# edi_1.net
KiCad netlist of a schematic drawn in EAGLE
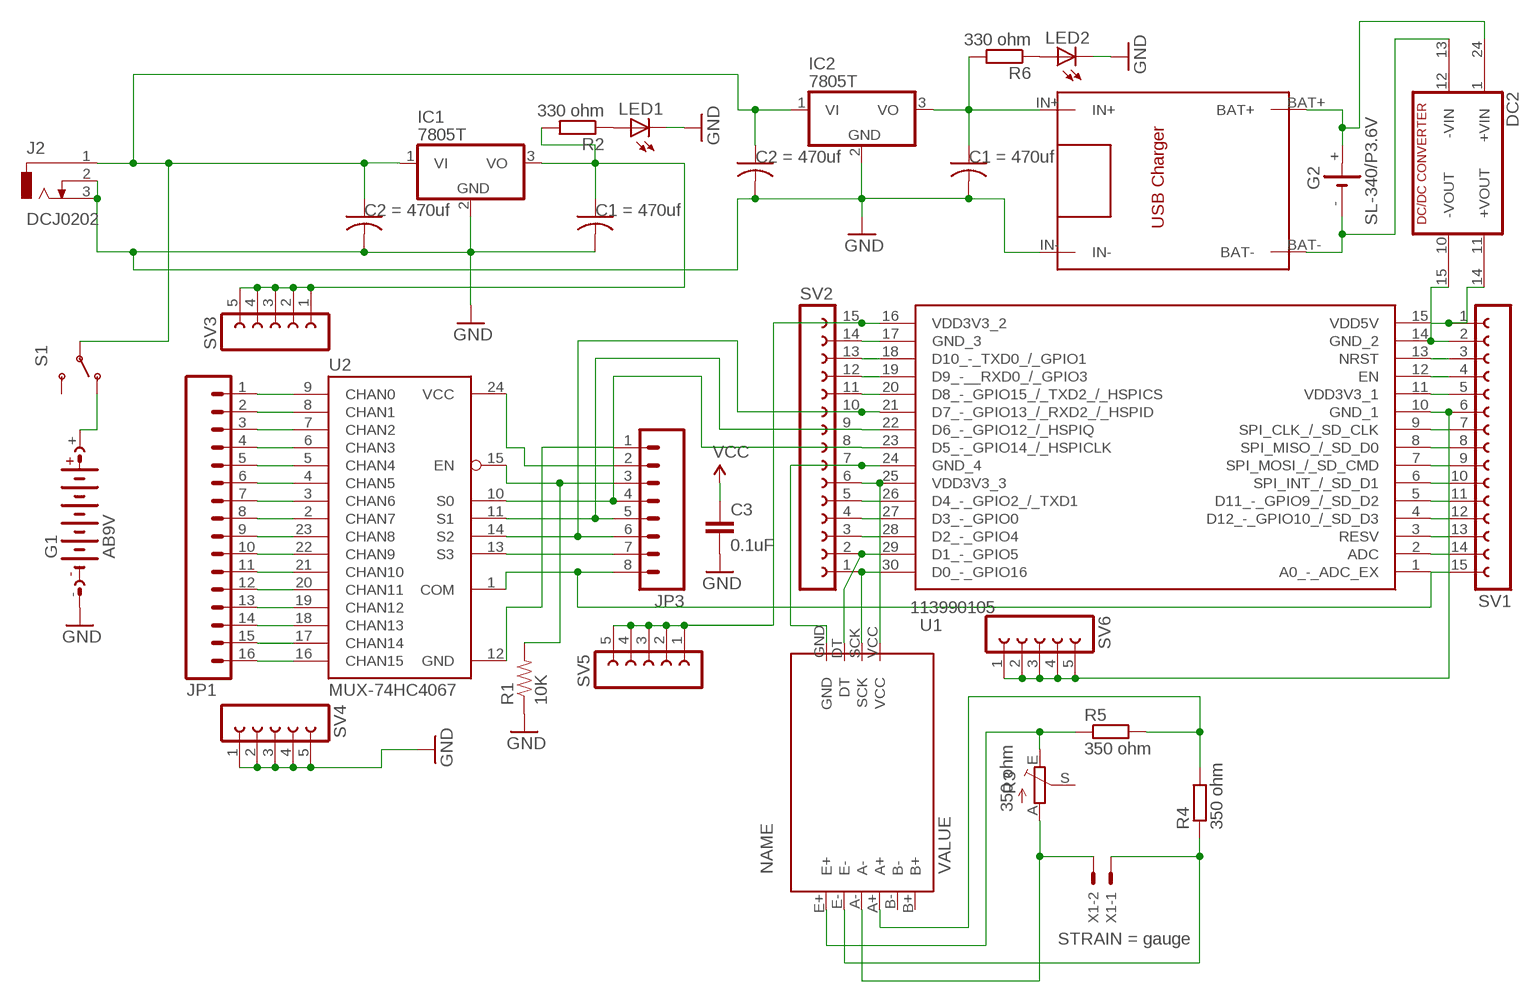
[diagram p0: schematic, sheet 1]

(export (version "E")
  (design (tool "Eeschema 10.0.6"))
  (components
    (comp (ref "C1")
      (value "C-US025-024X044")
      (footprint "eagle-import:C025-024X044")
      (fields (field (name "C2") "470uf"))
      (libsource (lib "eagle-import") (part "C-US025-024X044"))
    )
    (comp (ref "C2")
      (value "C-US025-024X044")
      (footprint "eagle-import:C025-024X044")
      (fields (field (name "C1") "470uf") (field (name "POPULARITY") "470uf"))
      (libsource (lib "eagle-import") (part "C-US025-024X044"))
    )
    (comp (ref "C3")
      (value "0.1uF")
      (footprint "eagle-import:0603")
      (libsource (lib "eagle-import") (part "CAP0603"))
    )
    (comp (ref "C4")
      (value "C-US025-024X044")
      (footprint "eagle-import:C025-024X044")
      (fields (field (name "C2") "470uf"))
      (libsource (lib "eagle-import") (part "C-US025-024X044"))
    )
    (comp (ref "C5")
      (value "C-US025-024X044")
      (footprint "eagle-import:C025-024X044")
      (fields (field (name "C1") "470uf") (field (name "POPULARITY") "470uf"))
      (libsource (lib "eagle-import") (part "C-US025-024X044"))
    )
    (comp (ref "DC2")
      (value "DC213R")
      (footprint "eagle-import:CMK")
      (libsource (lib "eagle-import") (part "DC213R"))
    )
    (comp (ref "G1")
      (value "AB9V")
      (footprint "eagle-import:AB9V")
      (libsource (lib "eagle-import") (part "AB9V"))
    )
    (comp (ref "G2")
      (value "SL-340/P3.6V")
      (footprint "eagle-import:SL-340_P3.6V")
      (libsource (lib "eagle-import") (part "SL-340/P3.6V"))
    )
    (comp (ref "IC1")
      (value "7805T")
      (footprint "eagle-import:TO220H")
      (libsource (lib "eagle-import") (part "78T05"))
    )
    (comp (ref "IC2")
      (value "7805T")
      (footprint "eagle-import:TO220H")
      (libsource (lib "eagle-import") (part "78T05"))
    )
    (comp (ref "J2")
      (value "DCJ0202")
      (footprint "eagle-import:DCJ0202")
      (libsource (lib "eagle-import") (part "DCJ0202"))
    )
    (comp (ref "JP1")
      (value "M16PTH")
      (footprint "eagle-import:1X16")
      (libsource (lib "eagle-import") (part "M16PTH"))
    )
    (comp (ref "JP3")
      (value "M081X08")
      (footprint "eagle-import:1X08")
      (libsource (lib "eagle-import") (part "M081X08"))
    )
    (comp (ref "LED1")
      (value "LEDLD260")
      (footprint "eagle-import:LD260")
      (libsource (lib "eagle-import") (part "LEDLD260"))
    )
    (comp (ref "LED2")
      (value "LEDLD260")
      (footprint "eagle-import:LD260")
      (libsource (lib "eagle-import") (part "LEDLD260"))
    )
    (comp (ref "R1")
      (value "10K")
      (footprint "eagle-import:0603")
      (libsource (lib "eagle-import") (part "RESISTOR0603"))
    )
    (comp (ref "R2")
      (value "330 ohm")
      (footprint "eagle-import:0204_5")
      (libsource (lib "eagle-import") (part "R-EU_0204/5"))
    )
    (comp (ref "R3")
      (value "350 ohm")
      (footprint "eagle-import:RJ9W")
      (libsource (lib "eagle-import") (part "TRIM_EU-RJ9W"))
    )
    (comp (ref "R4")
      (value "350 ohm")
      (footprint "eagle-import:0204_5")
      (libsource (lib "eagle-import") (part "R-EU_0204/5"))
    )
    (comp (ref "R5")
      (value "350 ohm")
      (footprint "eagle-import:0204_5")
      (libsource (lib "eagle-import") (part "R-EU_0204/5"))
    )
    (comp (ref "R6")
      (value "330 ohm")
      (footprint "eagle-import:0204_5")
      (libsource (lib "eagle-import") (part "R-EU_0204/5"))
    )
    (comp (ref "S1")
      (value "SWITCH-SPDTSMD")
      (footprint "eagle-import:SWITCH_SPDT_SMD")
      (libsource (lib "eagle-import") (part "SWITCH-SPDTSMD"))
    )
    (comp (ref "SV1")
      (value "FE15-1")
      (footprint "eagle-import:FE15")
      (libsource (lib "eagle-import") (part "FE15-1"))
    )
    (comp (ref "SV2")
      (value "FE15-1")
      (footprint "eagle-import:FE15")
      (libsource (lib "eagle-import") (part "FE15-1"))
    )
    (comp (ref "SV3")
      (value "FE05-1")
      (footprint "eagle-import:FE05-1")
      (libsource (lib "eagle-import") (part "FE05-1"))
    )
    (comp (ref "SV4")
      (value "FE05-1")
      (footprint "eagle-import:FE05-1")
      (libsource (lib "eagle-import") (part "FE05-1"))
    )
    (comp (ref "SV5")
      (value "FE05-1")
      (footprint "eagle-import:FE05-1")
      (libsource (lib "eagle-import") (part "FE05-1"))
    )
    (comp (ref "SV6")
      (value "FE05-1")
      (footprint "eagle-import:FE05-1")
      (libsource (lib "eagle-import") (part "FE05-1"))
    )
    (comp (ref "U$1")
      (value "TP4056")
      (footprint "eagle-import:TP4056")
      (libsource (lib "eagle-import") (part "TP4056"))
    )
    (comp (ref "U$2")
      (value "HX711A")
      (footprint "eagle-import:HX711")
      (libsource (lib "eagle-import") (part "HX711A"))
    )
    (comp (ref "U1")
      (value "113990105")
      (footprint "eagle-import:113990105")
      (fields (field (name "MOUSER_PART_NUMBER") "713-113990105"))
      (libsource (lib "eagle-import") (part "113990105"))
    )
    (comp (ref "U2")
      (value "MUX-74HC4067")
      (footprint "eagle-import:SSOP24")
      (libsource (lib "eagle-import") (part "MUX-74HC4067SMD"))
    )
    (comp (ref "X1")
      (value "22-23-2021")
      (footprint "eagle-import:22-23-2021")
      (fields (field (name "STRAIN") "gauge"))
      (libsource (lib "eagle-import") (part "22-23-2021"))
    )
  )
  (nets
    (net (code "1") (name "GND") (class "Default")
      (node (ref "C1") (pin "2") (pinfunction "2_2") (pintype "passive"))
      (node (ref "C2") (pin "2") (pinfunction "2_2") (pintype "passive"))
      (node (ref "C3") (pin "2") (pinfunction "2_2") (pintype "passive"))
      (node (ref "C4") (pin "2") (pinfunction "2_2") (pintype "passive"))
      (node (ref "C5") (pin "2") (pinfunction "2_2") (pintype "passive"))
      (node (ref "G1") (pin "-") (pinfunction "-_-") (pintype "passive"))
      (node (ref "IC1") (pin "2") (pinfunction "GND_2") (pintype "passive"))
      (node (ref "IC2") (pin "2") (pinfunction "GND_2") (pintype "passive"))
      (node (ref "J2") (pin "2") (pinfunction "2_2") (pintype "passive"))
      (node (ref "J2") (pin "3") (pinfunction "3_3") (pintype "passive"))
      (node (ref "LED1") (pin "K") (pinfunction "C_K") (pintype "passive"))
      (node (ref "LED2") (pin "K") (pinfunction "C_K") (pintype "passive"))
      (node (ref "R1") (pin "1") (pinfunction "1_1") (pintype "passive"))
      (node (ref "SV4") (pin "1") (pinfunction "1_1") (pintype "passive"))
      (node (ref "SV4") (pin "2") (pinfunction "2_2") (pintype "passive"))
      (node (ref "SV4") (pin "3") (pinfunction "3_3") (pintype "passive"))
      (node (ref "SV4") (pin "4") (pinfunction "4_4") (pintype "passive"))
      (node (ref "SV4") (pin "5") (pinfunction "5_5") (pintype "passive"))
      (node (ref "U$1") (pin "IN-") (pinfunction "IN-_IN-") (pintype "bidirectional"))
    )
    (net (code "2") (name "Net-(DC2-+VIN1)") (class "Default")
      (node (ref "DC2") (pin "24") (pinfunction "+VIN1_24") (pintype "passive"))
      (node (ref "G2") (pin "+") (pinfunction "+_+") (pintype "passive"))
      (node (ref "U$1") (pin "BAT+") (pinfunction "BAT+_BAT+") (pintype "bidirectional"))
    )
    (net (code "3") (name "Net-(DC2-+VOUT1)") (class "Default")
      (node (ref "DC2") (pin "14") (pinfunction "+VOUT1_14") (pintype "passive"))
      (node (ref "SV1") (pin "1") (pinfunction "1_1") (pintype "passive"))
      (node (ref "U1") (pin "15") (pinfunction "VDD5V_15") (pintype "power_in"))
    )
    (net (code "4") (name "Net-(DC2--VIN1)") (class "Default")
      (node (ref "DC2") (pin "13") (pinfunction "-VIN1_13") (pintype "passive"))
      (node (ref "G2") (pin "-") (pinfunction "-_-") (pintype "passive"))
      (node (ref "U$1") (pin "BAT-") (pinfunction "BAT-_BAT-") (pintype "bidirectional"))
    )
    (net (code "5") (name "Net-(DC2--VOUT1)") (class "Default")
      (node (ref "DC2") (pin "15") (pinfunction "-VOUT1_15") (pintype "passive"))
      (node (ref "SV1") (pin "2") (pinfunction "2_2") (pintype "passive"))
      (node (ref "U1") (pin "14") (pinfunction "GND_2_14") (pintype "power_in"))
    )
    (net (code "6") (name "Net-(IC1-VI)") (class "Default")
      (node (ref "C1") (pin "1") (pinfunction "1_1") (pintype "passive"))
      (node (ref "C4") (pin "1") (pinfunction "1_1") (pintype "passive"))
      (node (ref "IC1") (pin "1") (pinfunction "VI_1") (pintype "input"))
      (node (ref "IC2") (pin "1") (pinfunction "VI_1") (pintype "input"))
      (node (ref "J2") (pin "1") (pinfunction "1_1") (pintype "passive"))
      (node (ref "S1") (pin "2") (pinfunction "P_2") (pintype "passive"))
    )
    (net (code "7") (name "Net-(IC1-VO)") (class "Default")
      (node (ref "C2") (pin "1") (pinfunction "1_1") (pintype "passive"))
      (node (ref "IC1") (pin "3") (pinfunction "VO_3") (pintype "passive"))
      (node (ref "R2") (pin "2") (pinfunction "2_2") (pintype "passive"))
      (node (ref "SV3") (pin "1") (pinfunction "1_1") (pintype "passive"))
      (node (ref "SV3") (pin "2") (pinfunction "2_2") (pintype "passive"))
      (node (ref "SV3") (pin "3") (pinfunction "3_3") (pintype "passive"))
      (node (ref "SV3") (pin "4") (pinfunction "4_4") (pintype "passive"))
      (node (ref "SV3") (pin "5") (pinfunction "5_5") (pintype "passive"))
    )
    (net (code "8") (name "Net-(IC2-VO)") (class "Default")
      (node (ref "C5") (pin "1") (pinfunction "1_1") (pintype "passive"))
      (node (ref "IC2") (pin "3") (pinfunction "VO_3") (pintype "passive"))
      (node (ref "R6") (pin "2") (pinfunction "2_2") (pintype "passive"))
      (node (ref "U$1") (pin "IN+") (pinfunction "IN+_IN+") (pintype "bidirectional"))
    )
    (net (code "9") (name "Net-(LED1-PadA)") (class "Default")
      (node (ref "LED1") (pin "A") (pinfunction "A_A") (pintype "passive"))
      (node (ref "R2") (pin "1") (pinfunction "1_1") (pintype "passive"))
    )
    (net (code "10") (name "Net-(LED2-PadA)") (class "Default")
      (node (ref "LED2") (pin "A") (pinfunction "A_A") (pintype "passive"))
      (node (ref "R6") (pin "1") (pinfunction "1_1") (pintype "passive"))
    )
    (net (code "11") (name "Net-(R3-PadE)") (class "Default")
      (node (ref "R3") (pin "E") (pinfunction "E_E") (pintype "passive"))
      (node (ref "R5") (pin "1") (pinfunction "1_1") (pintype "passive"))
      (node (ref "U$2") (pin "E+") (pinfunction "E+_E+") (pintype "bidirectional"))
    )
    (net (code "12") (name "Net-(R4-Pad2)") (class "Default")
      (node (ref "R4") (pin "2") (pinfunction "2_2") (pintype "passive"))
      (node (ref "R5") (pin "2") (pinfunction "2_2") (pintype "passive"))
      (node (ref "U$2") (pin "A+") (pinfunction "A+_A+") (pintype "bidirectional"))
    )
    (net (code "13") (name "Net-(S1-O)") (class "Default")
      (node (ref "G1") (pin "+") (pinfunction "+_+") (pintype "passive"))
      (node (ref "S1") (pin "1") (pinfunction "O_1") (pintype "passive"))
    )
    (net (code "14") (name "Net-(U1-A0_-_ADC_EX)") (class "Default")
      (node (ref "JP3") (pin "8") (pinfunction "8_8") (pintype "passive"))
      (node (ref "SV1") (pin "15") (pinfunction "15_15") (pintype "passive"))
      (node (ref "U1") (pin "1") (pinfunction "A0_-_ADC_EX_1") (pintype "bidirectional"))
      (node (ref "U2") (pin "1") (pinfunction "COM_1") (pintype "bidirectional"))
    )
    (net (code "15") (name "Net-(U1-ADC)") (class "Default")
      (node (ref "SV1") (pin "14") (pinfunction "14_14") (pintype "passive"))
      (node (ref "U1") (pin "2") (pinfunction "ADC_2") (pintype "bidirectional"))
    )
    (net (code "16") (name "Net-(U1-D0_-_GPIO16)") (class "Default")
      (node (ref "SV2") (pin "1") (pinfunction "1_1") (pintype "passive"))
      (node (ref "U$2") (pin "SCK") (pinfunction "SCK_SCK") (pintype "bidirectional"))
      (node (ref "U1") (pin "30") (pinfunction "D0_-_GPIO16_30") (pintype "bidirectional"))
    )
    (net (code "17") (name "Net-(U1-D1_-_GPIO5)") (class "Default")
      (node (ref "SV2") (pin "2") (pinfunction "2_2") (pintype "passive"))
      (node (ref "U$2") (pin "DT") (pinfunction "DT_DT") (pintype "bidirectional"))
      (node (ref "U1") (pin "29") (pinfunction "D1_-_GPIO5_29") (pintype "bidirectional"))
    )
    (net (code "18") (name "Net-(U1-D2_-_GPIO4)") (class "Default")
      (node (ref "SV2") (pin "3") (pinfunction "3_3") (pintype "passive"))
      (node (ref "U1") (pin "28") (pinfunction "D2_-_GPIO4_28") (pintype "bidirectional"))
    )
    (net (code "19") (name "Net-(U1-D3_-_GPIO0)") (class "Default")
      (node (ref "SV2") (pin "4") (pinfunction "4_4") (pintype "passive"))
      (node (ref "U1") (pin "27") (pinfunction "D3_-_GPIO0_27") (pintype "bidirectional"))
    )
    (net (code "20") (name "Net-(U1-D4_-_GPIO2_{slash}_TXD1)") (class "Default")
      (node (ref "SV2") (pin "5") (pinfunction "5_5") (pintype "passive"))
      (node (ref "U1") (pin "26") (pinfunction "D4_-_GPIO2_/_TXD1_26") (pintype "bidirectional"))
    )
    (net (code "21") (name "Net-(U1-D5_-_GPIO14_{slash}_HSPICLK)") (class "Default")
      (node (ref "JP3") (pin "4") (pinfunction "4_4") (pintype "passive"))
      (node (ref "SV2") (pin "8") (pinfunction "8_8") (pintype "passive"))
      (node (ref "U1") (pin "23") (pinfunction "D5_-_GPIO14_/_HSPICLK_23") (pintype "bidirectional"))
      (node (ref "U2") (pin "10") (pinfunction "S0_10") (pintype "input"))
    )
    (net (code "22") (name "Net-(U1-D6_-_GPIO12_{slash}_HSPIQ)") (class "Default")
      (node (ref "JP3") (pin "5") (pinfunction "5_5") (pintype "passive"))
      (node (ref "SV2") (pin "9") (pinfunction "9_9") (pintype "passive"))
      (node (ref "U1") (pin "22") (pinfunction "D6_-_GPIO12_/_HSPIQ_22") (pintype "bidirectional"))
      (node (ref "U2") (pin "11") (pinfunction "S1_11") (pintype "input"))
    )
    (net (code "23") (name "Net-(U1-D7_-_GPIO13_{slash}_RXD2_{slash}_HSPID)") (class "Default")
      (node (ref "JP3") (pin "6") (pinfunction "6_6") (pintype "passive"))
      (node (ref "SV2") (pin "10") (pinfunction "10_10") (pintype "passive"))
      (node (ref "U1") (pin "21") (pinfunction "D7_-_GPIO13_/_RXD2_/_HSPID_21") (pintype "bidirectional"))
      (node (ref "U2") (pin "14") (pinfunction "S2_14") (pintype "input"))
    )
    (net (code "24") (name "Net-(U1-D8_-_GPIO15_{slash}_TXD2_{slash}_HSPICS)") (class "Default")
      (node (ref "SV2") (pin "11") (pinfunction "11_11") (pintype "passive"))
      (node (ref "U1") (pin "20") (pinfunction "D8_-_GPIO15_/_TXD2_/_HSPICS_20") (pintype "bidirectional"))
    )
    (net (code "25") (name "Net-(U1-D9_-__RXD0_{slash}_GPIO3)") (class "Default")
      (node (ref "SV2") (pin "12") (pinfunction "12_12") (pintype "passive"))
      (node (ref "U1") (pin "19") (pinfunction "D9_-__RXD0_/_GPIO3_19") (pintype "bidirectional"))
    )
    (net (code "26") (name "Net-(U1-D10_-_TXD0_{slash}_GPIO1)") (class "Default")
      (node (ref "SV2") (pin "13") (pinfunction "13_13") (pintype "passive"))
      (node (ref "U1") (pin "18") (pinfunction "D10_-_TXD0_/_GPIO1_18") (pintype "bidirectional"))
    )
    (net (code "27") (name "Net-(U1-D11_-_GPIO9_{slash}_SD_D2)") (class "Default")
      (node (ref "SV1") (pin "11") (pinfunction "11_11") (pintype "passive"))
      (node (ref "U1") (pin "5") (pinfunction "D11_-_GPIO9_/_SD_D2_5") (pintype "bidirectional"))
    )
    (net (code "28") (name "Net-(U1-D12_-_GPIO10_{slash}_SD_D3)") (class "Default")
      (node (ref "SV1") (pin "12") (pinfunction "12_12") (pintype "passive"))
      (node (ref "U1") (pin "4") (pinfunction "D12_-_GPIO10_/_SD_D3_4") (pintype "bidirectional"))
    )
    (net (code "29") (name "Net-(U1-EN)") (class "Default")
      (node (ref "SV1") (pin "4") (pinfunction "4_4") (pintype "passive"))
      (node (ref "U1") (pin "12") (pinfunction "EN_12") (pintype "input"))
    )
    (net (code "30") (name "Net-(U1-GND_1)") (class "Default")
      (node (ref "SV1") (pin "6") (pinfunction "6_6") (pintype "passive"))
      (node (ref "SV6") (pin "1") (pinfunction "1_1") (pintype "passive"))
      (node (ref "SV6") (pin "2") (pinfunction "2_2") (pintype "passive"))
      (node (ref "SV6") (pin "3") (pinfunction "3_3") (pintype "passive"))
      (node (ref "SV6") (pin "4") (pinfunction "4_4") (pintype "passive"))
      (node (ref "SV6") (pin "5") (pinfunction "5_5") (pintype "passive"))
      (node (ref "U1") (pin "10") (pinfunction "GND_1_10") (pintype "power_in"))
    )
    (net (code "31") (name "Net-(U1-GND_3)") (class "Default")
      (node (ref "SV2") (pin "14") (pinfunction "14_14") (pintype "passive"))
      (node (ref "U1") (pin "17") (pinfunction "GND_3_17") (pintype "power_in"))
    )
    (net (code "32") (name "Net-(U1-GND_4)") (class "Default")
      (node (ref "SV2") (pin "7") (pinfunction "7_7") (pintype "passive"))
      (node (ref "U$2") (pin "GND") (pinfunction "GND_GND") (pintype "bidirectional"))
      (node (ref "U1") (pin "24") (pinfunction "GND_4_24") (pintype "power_in"))
    )
    (net (code "33") (name "Net-(U1-NRST)") (class "Default")
      (node (ref "SV1") (pin "3") (pinfunction "3_3") (pintype "passive"))
      (node (ref "U1") (pin "13") (pinfunction "NRST_13") (pintype "input"))
    )
    (net (code "34") (name "Net-(U1-RESV)") (class "Default")
      (node (ref "SV1") (pin "13") (pinfunction "13_13") (pintype "passive"))
      (node (ref "U1") (pin "3") (pinfunction "RESV_3") (pintype "bidirectional"))
    )
    (net (code "35") (name "Net-(U1-SPI_CLK_{slash}_SD_CLK)") (class "Default")
      (node (ref "SV1") (pin "7") (pinfunction "7_7") (pintype "passive"))
      (node (ref "U1") (pin "9") (pinfunction "SPI_CLK_/_SD_CLK_9") (pintype "bidirectional"))
    )
    (net (code "36") (name "Net-(U1-SPI_INT_{slash}_SD_D1)") (class "Default")
      (node (ref "SV1") (pin "10") (pinfunction "10_10") (pintype "passive"))
      (node (ref "U1") (pin "6") (pinfunction "SPI_INT_/_SD_D1_6") (pintype "bidirectional"))
    )
    (net (code "37") (name "Net-(U1-SPI_MISO_{slash}_SD_D0)") (class "Default")
      (node (ref "SV1") (pin "8") (pinfunction "8_8") (pintype "passive"))
      (node (ref "U1") (pin "8") (pinfunction "SPI_MISO_/_SD_D0_8") (pintype "bidirectional"))
    )
    (net (code "38") (name "Net-(U1-SPI_MOSI_{slash}_SD_CMD)") (class "Default")
      (node (ref "SV1") (pin "9") (pinfunction "9_9") (pintype "passive"))
      (node (ref "U1") (pin "7") (pinfunction "SPI_MOSI_/_SD_CMD_7") (pintype "bidirectional"))
    )
    (net (code "39") (name "Net-(U1-VDD3V3_1)") (class "Default")
      (node (ref "SV1") (pin "5") (pinfunction "5_5") (pintype "passive"))
      (node (ref "U1") (pin "11") (pinfunction "VDD3V3_1_11") (pintype "power_in"))
    )
    (net (code "40") (name "Net-(U1-VDD3V3_2)") (class "Default")
      (node (ref "SV2") (pin "15") (pinfunction "15_15") (pintype "passive"))
      (node (ref "SV5") (pin "1") (pinfunction "1_1") (pintype "passive"))
      (node (ref "SV5") (pin "2") (pinfunction "2_2") (pintype "passive"))
      (node (ref "SV5") (pin "3") (pinfunction "3_3") (pintype "passive"))
      (node (ref "SV5") (pin "4") (pinfunction "4_4") (pintype "passive"))
      (node (ref "SV5") (pin "5") (pinfunction "5_5") (pintype "passive"))
      (node (ref "U1") (pin "16") (pinfunction "VDD3V3_2_16") (pintype "power_in"))
    )
    (net (code "41") (name "Net-(U1-VDD3V3_3)") (class "Default")
      (node (ref "SV2") (pin "6") (pinfunction "6_6") (pintype "passive"))
      (node (ref "U$2") (pin "VCC") (pinfunction "VCC_VCC") (pintype "bidirectional"))
      (node (ref "U1") (pin "25") (pinfunction "VDD3V3_3_25") (pintype "power_in"))
    )
    (net (code "42") (name "Net-(U2-CHAN0)") (class "Default")
      (node (ref "JP1") (pin "1") (pinfunction "1_1") (pintype "passive"))
      (node (ref "U2") (pin "9") (pinfunction "CHAN0_9") (pintype "bidirectional"))
    )
    (net (code "43") (name "Net-(U2-CHAN1)") (class "Default")
      (node (ref "JP1") (pin "2") (pinfunction "2_2") (pintype "passive"))
      (node (ref "U2") (pin "8") (pinfunction "CHAN1_8") (pintype "bidirectional"))
    )
    (net (code "44") (name "Net-(U2-CHAN2)") (class "Default")
      (node (ref "JP1") (pin "3") (pinfunction "3_3") (pintype "passive"))
      (node (ref "U2") (pin "7") (pinfunction "CHAN2_7") (pintype "bidirectional"))
    )
    (net (code "45") (name "Net-(U2-CHAN3)") (class "Default")
      (node (ref "JP1") (pin "4") (pinfunction "4_4") (pintype "passive"))
      (node (ref "U2") (pin "6") (pinfunction "CHAN3_6") (pintype "bidirectional"))
    )
    (net (code "46") (name "Net-(U2-CHAN4)") (class "Default")
      (node (ref "JP1") (pin "5") (pinfunction "5_5") (pintype "passive"))
      (node (ref "U2") (pin "5") (pinfunction "CHAN4_5") (pintype "bidirectional"))
    )
    (net (code "47") (name "Net-(U2-CHAN5)") (class "Default")
      (node (ref "JP1") (pin "6") (pinfunction "6_6") (pintype "passive"))
      (node (ref "U2") (pin "4") (pinfunction "CHAN5_4") (pintype "bidirectional"))
    )
    (net (code "48") (name "Net-(U2-CHAN6)") (class "Default")
      (node (ref "JP1") (pin "7") (pinfunction "7_7") (pintype "passive"))
      (node (ref "U2") (pin "3") (pinfunction "CHAN6_3") (pintype "bidirectional"))
    )
    (net (code "49") (name "Net-(U2-CHAN7)") (class "Default")
      (node (ref "JP1") (pin "8") (pinfunction "8_8") (pintype "passive"))
      (node (ref "U2") (pin "2") (pinfunction "CHAN7_2") (pintype "bidirectional"))
    )
    (net (code "50") (name "Net-(U2-CHAN8)") (class "Default")
      (node (ref "JP1") (pin "9") (pinfunction "9_9") (pintype "passive"))
      (node (ref "U2") (pin "23") (pinfunction "CHAN8_23") (pintype "bidirectional"))
    )
    (net (code "51") (name "Net-(U2-CHAN9)") (class "Default")
      (node (ref "JP1") (pin "10") (pinfunction "10_10") (pintype "passive"))
      (node (ref "U2") (pin "22") (pinfunction "CHAN9_22") (pintype "bidirectional"))
    )
    (net (code "52") (name "Net-(U2-CHAN10)") (class "Default")
      (node (ref "JP1") (pin "11") (pinfunction "11_11") (pintype "passive"))
      (node (ref "U2") (pin "21") (pinfunction "CHAN10_21") (pintype "bidirectional"))
    )
    (net (code "53") (name "Net-(U2-CHAN11)") (class "Default")
      (node (ref "JP1") (pin "12") (pinfunction "12_12") (pintype "passive"))
      (node (ref "U2") (pin "20") (pinfunction "CHAN11_20") (pintype "bidirectional"))
    )
    (net (code "54") (name "Net-(U2-CHAN12)") (class "Default")
      (node (ref "JP1") (pin "13") (pinfunction "13_13") (pintype "passive"))
      (node (ref "U2") (pin "19") (pinfunction "CHAN12_19") (pintype "bidirectional"))
    )
    (net (code "55") (name "Net-(U2-CHAN13)") (class "Default")
      (node (ref "JP1") (pin "14") (pinfunction "14_14") (pintype "passive"))
      (node (ref "U2") (pin "18") (pinfunction "CHAN13_18") (pintype "bidirectional"))
    )
    (net (code "56") (name "Net-(U2-CHAN14)") (class "Default")
      (node (ref "JP1") (pin "15") (pinfunction "15_15") (pintype "passive"))
      (node (ref "U2") (pin "17") (pinfunction "CHAN14_17") (pintype "bidirectional"))
    )
    (net (code "57") (name "Net-(U2-CHAN15)") (class "Default")
      (node (ref "JP1") (pin "16") (pinfunction "16_16") (pintype "passive"))
      (node (ref "U2") (pin "16") (pinfunction "CHAN15_16") (pintype "bidirectional"))
    )
    (net (code "58") (name "Net-(U2-EN)") (class "Default")
      (node (ref "JP3") (pin "3") (pinfunction "3_3") (pintype "passive"))
      (node (ref "R1") (pin "2") (pinfunction "2_2") (pintype "passive"))
      (node (ref "U2") (pin "15") (pinfunction "EN_15") (pintype "input"))
    )
    (net (code "59") (name "Net-(U2-GND)") (class "Default")
      (node (ref "JP3") (pin "1") (pinfunction "1_1") (pintype "passive"))
      (node (ref "U2") (pin "12") (pinfunction "GND_12") (pintype "bidirectional"))
    )
    (net (code "60") (name "Net-(U2-S3)") (class "Default")
      (node (ref "JP3") (pin "7") (pinfunction "7_7") (pintype "passive"))
      (node (ref "U2") (pin "13") (pinfunction "S3_13") (pintype "input"))
    )
    (net (code "61") (name "Net-(X1A-S)") (class "Default")
      (node (ref "R4") (pin "1") (pinfunction "1_1") (pintype "passive"))
      (node (ref "U$2") (pin "E-") (pinfunction "E-_E-") (pintype "bidirectional"))
      (node (ref "X1") (pin "1") (pinfunction "S_1") (pintype "passive"))
    )
    (net (code "62") (name "Net-(X1B-S)") (class "Default")
      (node (ref "R3") (pin "A") (pinfunction "A_A") (pintype "passive"))
      (node (ref "U$2") (pin "A-") (pinfunction "A-_A-") (pintype "bidirectional"))
      (node (ref "X1") (pin "2") (pinfunction "S_2") (pintype "passive"))
    )
    (net (code "63") (name "VCC") (class "Default")
      (node (ref "C3") (pin "1") (pinfunction "1_1") (pintype "passive"))
      (node (ref "JP3") (pin "2") (pinfunction "2_2") (pintype "passive"))
      (node (ref "U2") (pin "24") (pinfunction "VCC_24") (pintype "bidirectional"))
    )
    (net (code "64") (name "unconnected-(DC2-+VIN-Pad1)") (class "Default")
      (node (ref "DC2") (pin "1") (pinfunction "+VIN_1") (pintype "passive"))
    )
    (net (code "65") (name "unconnected-(DC2-+VOUT-Pad11)") (class "Default")
      (node (ref "DC2") (pin "11") (pinfunction "+VOUT_11") (pintype "passive"))
    )
    (net (code "66") (name "unconnected-(DC2--VIN-Pad12)") (class "Default")
      (node (ref "DC2") (pin "12") (pinfunction "-VIN_12") (pintype "passive"))
    )
    (net (code "67") (name "unconnected-(DC2--VOUT-Pad10)") (class "Default")
      (node (ref "DC2") (pin "10") (pinfunction "-VOUT_10") (pintype "passive"))
    )
    (net (code "68") (name "unconnected-(R3-PadS)") (class "Default")
      (node (ref "R3") (pin "S") (pinfunction "S_S") (pintype "passive"))
    )
    (net (code "69") (name "unconnected-(S1-S-Pad3)") (class "Default")
      (node (ref "S1") (pin "3") (pinfunction "S_3") (pintype "passive"))
    )
    (net (code "70") (name "unconnected-(U$2-PadB+)") (class "Default")
      (node (ref "U$2") (pin "B+") (pinfunction "B+_B+") (pintype "bidirectional"))
    )
    (net (code "71") (name "unconnected-(U$2-PadB-)") (class "Default")
      (node (ref "U$2") (pin "B-") (pinfunction "B-_B-") (pintype "bidirectional"))
    )
  )
)
